# seven_segment_driver.net
KiCad netlist of a schematic drawn in Altium Designer
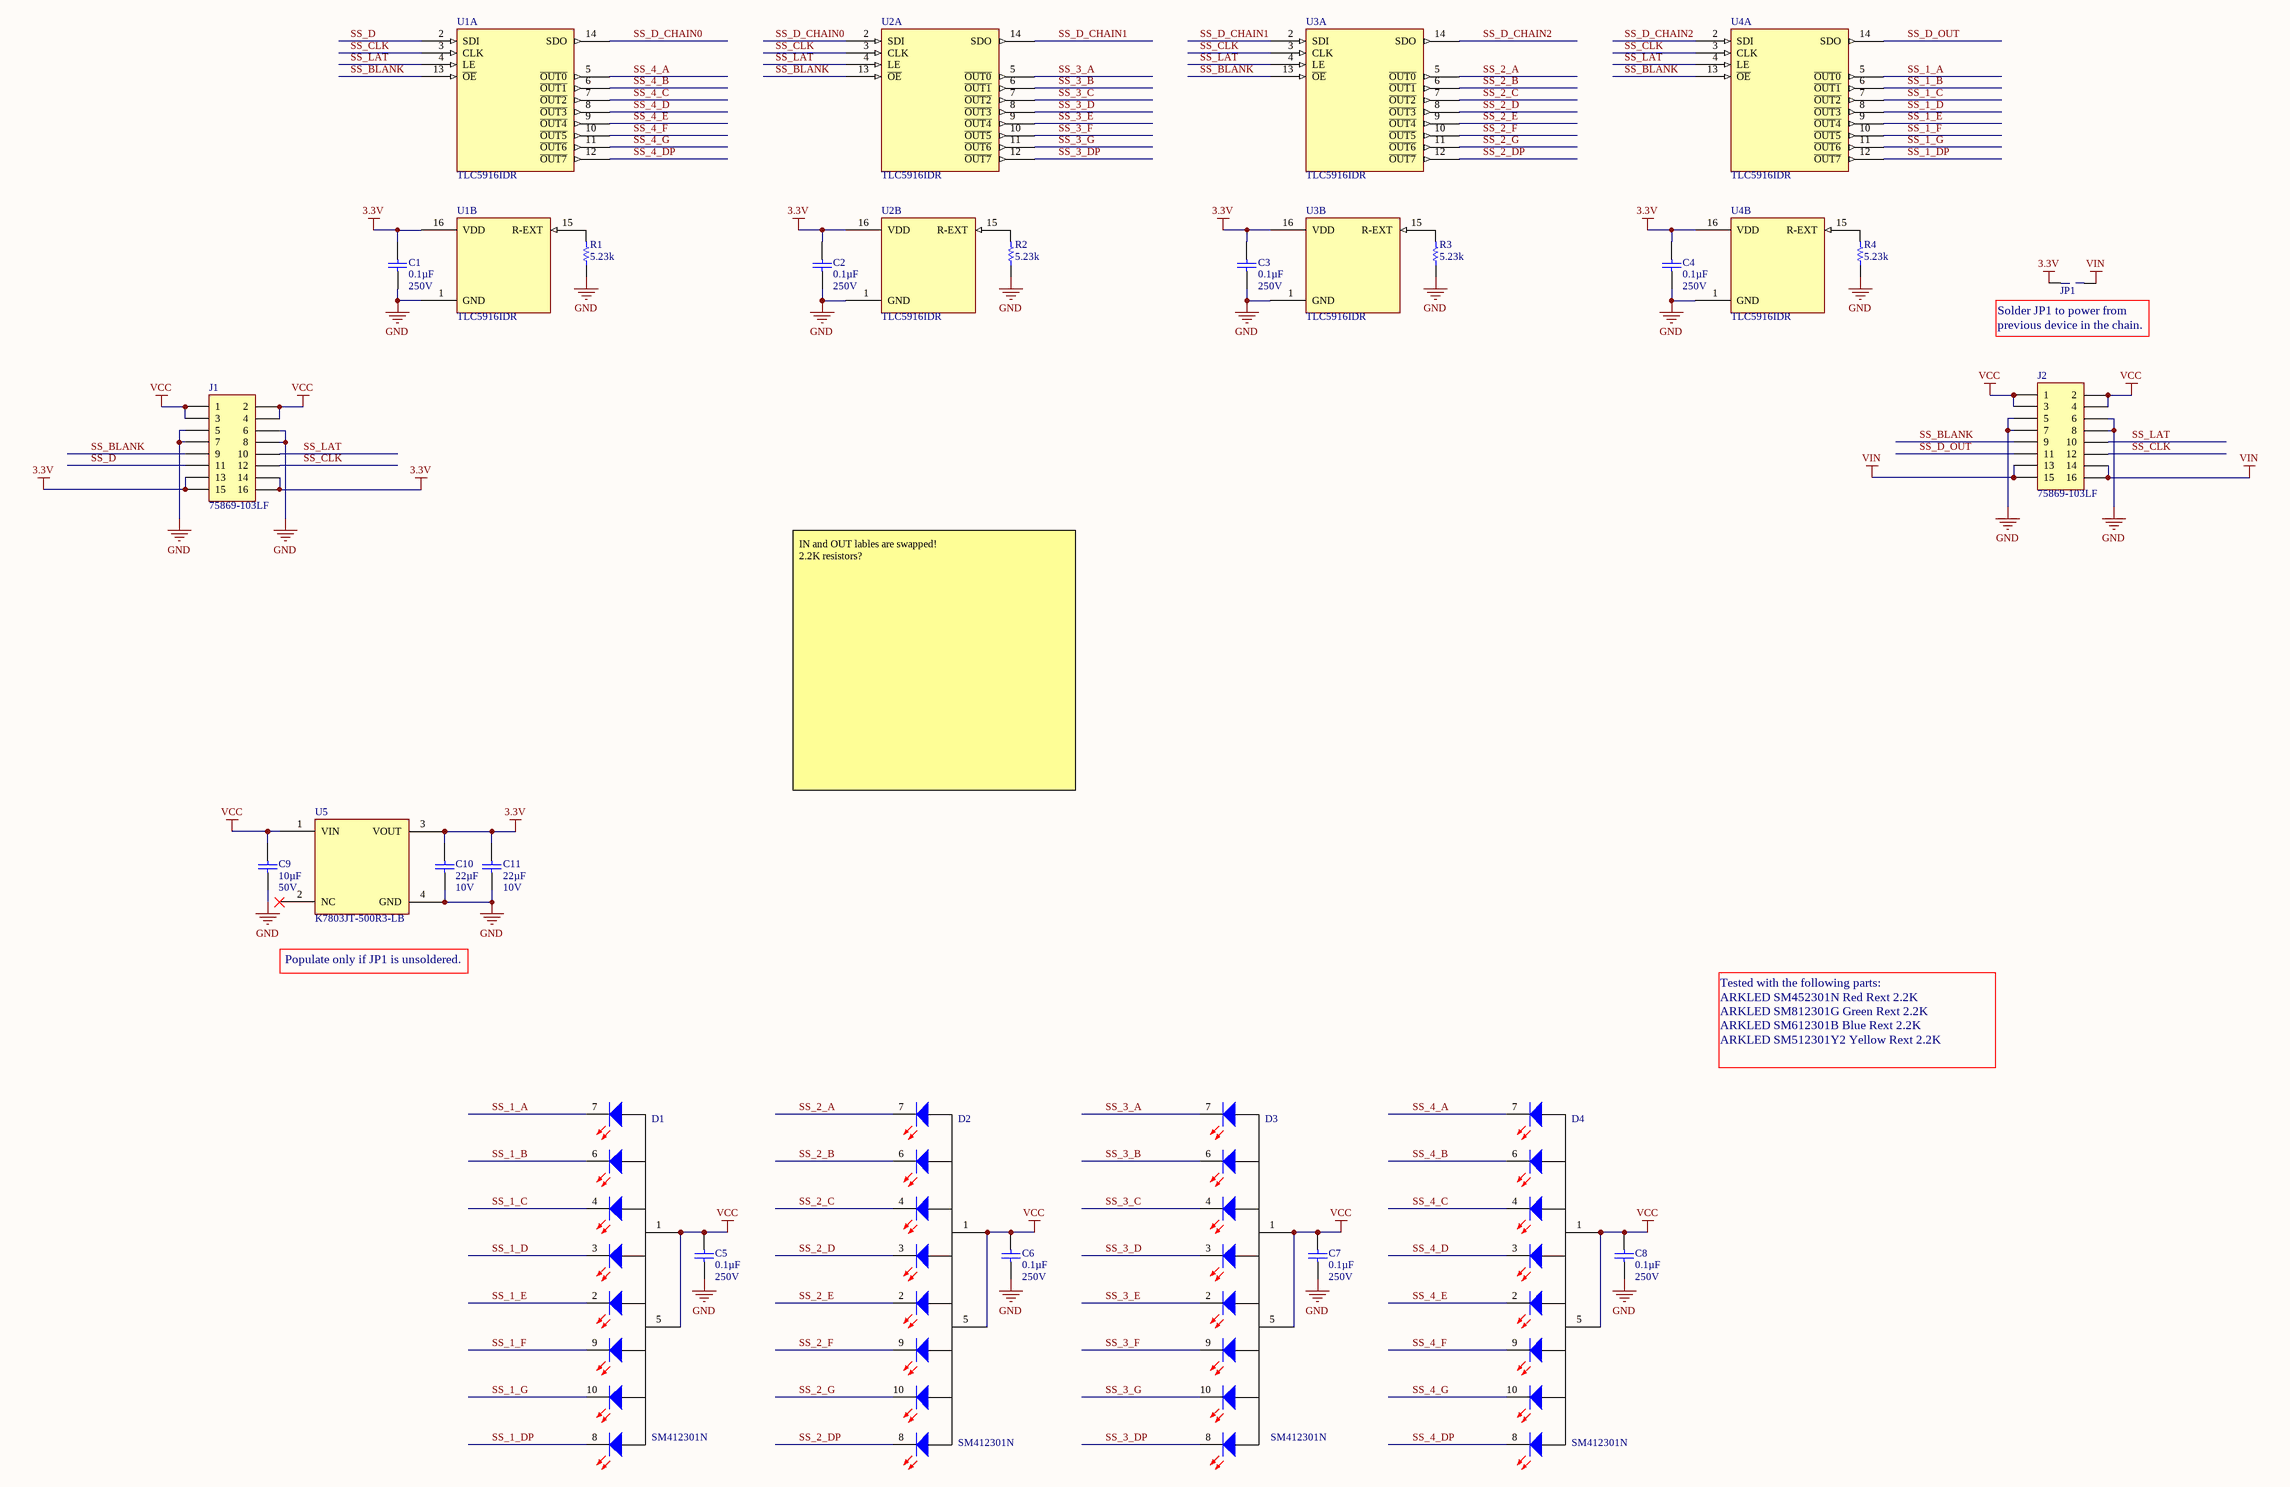
[diagram p0: seven_segment_driver.SchDoc]

(export (version "E")
  (design (tool "Eeschema 10.0.6"))
  (components
    (comp (ref "C1")
      (value "0.1µF")
      (footprint "Chip0805")
      (description "CAP CER 0.1UF 250V 10% X7T 0805")
      (fields
        (field (name "VOLTAGE") "250V")
        (field (name "PARTNUMBER") "C2012X7T2E104K125AA")
        (field (name "MANUFACTURER") "TDK Corporation")
      )
      (libsource (lib "Passives") (part "CAP"))
    )
    (comp (ref "C2")
      (value "0.1µF")
      (footprint "Chip0805")
      (description "CAP CER 0.1UF 250V 10% X7T 0805")
      (fields
        (field (name "VOLTAGE") "250V")
        (field (name "PARTNUMBER") "C2012X7T2E104K125AA")
        (field (name "MANUFACTURER") "TDK Corporation")
      )
      (libsource (lib "Passives") (part "CAP"))
    )
    (comp (ref "C3")
      (value "0.1µF")
      (footprint "Chip0805")
      (description "CAP CER 0.1UF 250V 10% X7T 0805")
      (fields
        (field (name "VOLTAGE") "250V")
        (field (name "PARTNUMBER") "C2012X7T2E104K125AA")
        (field (name "MANUFACTURER") "TDK Corporation")
      )
      (libsource (lib "Passives") (part "CAP"))
    )
    (comp (ref "C4")
      (value "0.1µF")
      (footprint "Chip0805")
      (description "CAP CER 0.1UF 250V 10% X7T 0805")
      (fields
        (field (name "VOLTAGE") "250V")
        (field (name "PARTNUMBER") "C2012X7T2E104K125AA")
        (field (name "MANUFACTURER") "TDK Corporation")
      )
      (libsource (lib "Passives") (part "CAP"))
    )
    (comp (ref "C5")
      (value "0.1µF")
      (footprint "Chip0805")
      (description "CAP CER 0.1UF 250V 10% X7T 0805")
      (fields
        (field (name "VOLTAGE") "250V")
        (field (name "PARTNUMBER") "C2012X7T2E104K125AA")
        (field (name "MANUFACTURER") "TDK Corporation")
      )
      (libsource (lib "Passives") (part "CAP"))
    )
    (comp (ref "C6")
      (value "0.1µF")
      (footprint "Chip0805")
      (description "CAP CER 0.1UF 250V 10% X7T 0805")
      (fields
        (field (name "VOLTAGE") "250V")
        (field (name "PARTNUMBER") "C2012X7T2E104K125AA")
        (field (name "MANUFACTURER") "TDK Corporation")
      )
      (libsource (lib "Passives") (part "CAP"))
    )
    (comp (ref "C7")
      (value "0.1µF")
      (footprint "Chip0805")
      (description "CAP CER 0.1UF 250V 10% X7T 0805")
      (fields
        (field (name "VOLTAGE") "250V")
        (field (name "PARTNUMBER") "C2012X7T2E104K125AA")
        (field (name "MANUFACTURER") "TDK Corporation")
      )
      (libsource (lib "Passives") (part "CAP"))
    )
    (comp (ref "C8")
      (value "0.1µF")
      (footprint "Chip0805")
      (description "CAP CER 0.1UF 250V 10% X7T 0805")
      (fields
        (field (name "VOLTAGE") "250V")
        (field (name "PARTNUMBER") "C2012X7T2E104K125AA")
        (field (name "MANUFACTURER") "TDK Corporation")
      )
      (libsource (lib "Passives") (part "CAP"))
    )
    (comp (ref "C9")
      (value "10µF")
      (footprint "Chip1206")
      (description "CAP CER 10UF 50V 10% X5R 1206")
      (fields
        (field (name "VOLTAGE") "50V")
        (field (name "PARTNUMBER") "C3216X5R1H106K160AB")
        (field (name "MANUFACTURER") "TDK Corporation")
      )
      (libsource (lib "Passives") (part "CAP"))
    )
    (comp (ref "C10")
      (value "22µF")
      (footprint "Chip0805")
      (description "CAP CER 22UF 10V 20% X5R 0805")
      (fields
        (field (name "VOLTAGE") "10V")
        (field (name "PARTNUMBER") "C2012X5R1A226M085AC")
        (field (name "MANUFACTURER") "TDK Corporation")
      )
      (libsource (lib "Passives") (part "CAP"))
    )
    (comp (ref "C11")
      (value "22µF")
      (footprint "Chip0805")
      (description "CAP CER 22UF 10V 20% X5R 0805")
      (fields
        (field (name "VOLTAGE") "10V")
        (field (name "PARTNUMBER") "C2012X5R1A226M085AC")
        (field (name "MANUFACTURER") "TDK Corporation")
      )
      (libsource (lib "Passives") (part "CAP"))
    )
    (comp (ref "D1")
      (value "SM412301N")
      (footprint "seven_segment_2p3")
      (description "SEGMENTS DISPLAY 2.3\" COMMON ANODE")
      (fields (field (name "MANUFACTURER") "ARKLED"))
      (libsource (lib "Optoelectronics") (part "SEVEN_SEGMENT_ANODE"))
    )
    (comp (ref "D2")
      (value "SM412301N")
      (footprint "seven_segment_2p3")
      (description "SEGMENTS DISPLAY 2.3\" COMMON ANODE")
      (fields (field (name "MANUFACTURER") "ARKLED"))
      (libsource (lib "Optoelectronics") (part "SEVEN_SEGMENT_ANODE"))
    )
    (comp (ref "D3")
      (value "SM412301N")
      (footprint "seven_segment_2p3")
      (description "SEGMENTS DISPLAY 2.3\" COMMON ANODE")
      (fields (field (name "MANUFACTURER") "ARKLED"))
      (libsource (lib "Optoelectronics") (part "SEVEN_SEGMENT_ANODE"))
    )
    (comp (ref "D4")
      (value "SM412301N")
      (footprint "seven_segment_2p3")
      (description "SEGMENTS DISPLAY 2.3\" COMMON ANODE")
      (fields (field (name "MANUFACTURER") "ARKLED"))
      (libsource (lib "Optoelectronics") (part "SEVEN_SEGMENT_ANODE"))
    )
    (comp (ref "J1")
      (value "75869-103LF")
      (footprint "IDC_100_2x8")
      (description "CONN HEADER 16POS DUAL VERT PCB")
      (fields (field (name "MANUFACTURER") "FCI"))
      (libsource (lib "Connectors") (part "HEADER_2x8_ALT"))
    )
    (comp (ref "J2")
      (value "75869-103LF")
      (footprint "IDC_100_2x8")
      (description "CONN HEADER 16POS DUAL VERT PCB")
      (fields (field (name "MANUFACTURER") "FCI"))
      (libsource (lib "Connectors") (part "HEADER_2x8_ALT"))
    )
    (comp (ref "JP1")
      (value "JUMMPER_NO_CIRCLE")
      (footprint "JUMMPER_NO_CIRCLE")
      (libsource (lib "Mechanical") (part "JUMPER_NO"))
    )
    (comp (ref "R1")
      (value "5.23k")
      (footprint "Chip0805")
      (description "RES 5.23K OHM 1/8W 1% 0805 SMD")
      (fields (field (name "PARTNUMBER") "CRCW08055K23FKEA") (field (name "MANUFACTURER") "Vishay Dale"))
      (libsource (lib "Passives") (part "RES"))
    )
    (comp (ref "R2")
      (value "5.23k")
      (footprint "Chip0805")
      (description "RES 5.23K OHM 1/8W 1% 0805 SMD")
      (fields (field (name "PARTNUMBER") "CRCW08055K23FKEA") (field (name "MANUFACTURER") "Vishay Dale"))
      (libsource (lib "Passives") (part "RES"))
    )
    (comp (ref "R3")
      (value "5.23k")
      (footprint "Chip0805")
      (description "RES 5.23K OHM 1/8W 1% 0805 SMD")
      (fields (field (name "PARTNUMBER") "CRCW08055K23FKEA") (field (name "MANUFACTURER") "Vishay Dale"))
      (libsource (lib "Passives") (part "RES"))
    )
    (comp (ref "R4")
      (value "5.23k")
      (footprint "Chip0805")
      (description "RES 5.23K OHM 1/8W 1% 0805 SMD")
      (fields (field (name "PARTNUMBER") "CRCW08055K23FKEA") (field (name "MANUFACTURER") "Vishay Dale"))
      (libsource (lib "Passives") (part "RES"))
    )
    (comp (ref "U1")
      (value "TLC5916IDR")
      (footprint "16-SOIC")
      (description "IC LED DRVR LINEAR 120MA 16SOIC")
      (fields (field (name "MANUFACTURER") "Texas Instruments"))
      (libsource (lib "ICs") (part "TI_TLC591x"))
    )
    (comp (ref "U2")
      (value "TLC5916IDR")
      (footprint "16-SOIC")
      (description "IC LED DRVR LINEAR 120MA 16SOIC")
      (fields (field (name "MANUFACTURER") "Texas Instruments"))
      (libsource (lib "ICs") (part "TI_TLC591x"))
    )
    (comp (ref "U3")
      (value "TLC5916IDR")
      (footprint "16-SOIC")
      (description "IC LED DRVR LINEAR 120MA 16SOIC")
      (fields (field (name "MANUFACTURER") "Texas Instruments"))
      (libsource (lib "ICs") (part "TI_TLC591x"))
    )
    (comp (ref "U4")
      (value "TLC5916IDR")
      (footprint "16-SOIC")
      (description "IC LED DRVR LINEAR 120MA 16SOIC")
      (fields (field (name "MANUFACTURER") "Texas Instruments"))
      (libsource (lib "ICs") (part "TI_TLC591x"))
    )
    (comp (ref "U5")
      (value "K7803JT-500R3-LB")
      (footprint "MORNSUN_K78XXJT-500R3-LB")
      (description "LINEAR REGULATOR REPLACEMENT DC")
      (fields (field (name "MANUFACTURER") "Mornsun America, LLC"))
      (libsource (lib "ICs") (part "MORNSUN_K78XXJT-500R3-LB"))
    )
  )
  (nets
    (net (code "1") (name "/SS_1_A") (class "Default")
      (node (ref "D1") (pin "7") (pinfunction "A_7") (pintype "passive"))
      (node (ref "U4") (pin "5") (pinfunction "~{OUT0}_5") (pintype "output"))
    )
    (net (code "2") (name "/SS_1_B") (class "Default")
      (node (ref "D1") (pin "6") (pinfunction "B_6") (pintype "passive"))
      (node (ref "U4") (pin "6") (pinfunction "~{OUT1}_6") (pintype "output"))
    )
    (net (code "3") (name "/SS_1_C") (class "Default")
      (node (ref "D1") (pin "4") (pinfunction "C_4") (pintype "passive"))
      (node (ref "U4") (pin "7") (pinfunction "~{OUT2}_7") (pintype "output"))
    )
    (net (code "4") (name "/SS_1_D") (class "Default")
      (node (ref "D1") (pin "3") (pinfunction "D_3") (pintype "passive"))
      (node (ref "U4") (pin "8") (pinfunction "~{OUT3}_8") (pintype "output"))
    )
    (net (code "5") (name "/SS_1_DP") (class "Default")
      (node (ref "D1") (pin "8") (pinfunction "DP_8") (pintype "passive"))
      (node (ref "U4") (pin "12") (pinfunction "~{OUT7}_12") (pintype "output"))
    )
    (net (code "6") (name "/SS_1_E") (class "Default")
      (node (ref "D1") (pin "2") (pinfunction "E_2") (pintype "passive"))
      (node (ref "U4") (pin "9") (pinfunction "~{OUT4}_9") (pintype "output"))
    )
    (net (code "7") (name "/SS_1_F") (class "Default")
      (node (ref "D1") (pin "9") (pinfunction "F_9") (pintype "passive"))
      (node (ref "U4") (pin "10") (pinfunction "~{OUT5}_10") (pintype "output"))
    )
    (net (code "8") (name "/SS_1_G") (class "Default")
      (node (ref "D1") (pin "10") (pinfunction "G_10") (pintype "passive"))
      (node (ref "U4") (pin "11") (pinfunction "~{OUT6}_11") (pintype "output"))
    )
    (net (code "9") (name "/SS_2_A") (class "Default")
      (node (ref "D2") (pin "7") (pinfunction "A_7") (pintype "passive"))
      (node (ref "U3") (pin "5") (pinfunction "~{OUT0}_5") (pintype "output"))
    )
    (net (code "10") (name "/SS_2_B") (class "Default")
      (node (ref "D2") (pin "6") (pinfunction "B_6") (pintype "passive"))
      (node (ref "U3") (pin "6") (pinfunction "~{OUT1}_6") (pintype "output"))
    )
    (net (code "11") (name "/SS_2_C") (class "Default")
      (node (ref "D2") (pin "4") (pinfunction "C_4") (pintype "passive"))
      (node (ref "U3") (pin "7") (pinfunction "~{OUT2}_7") (pintype "output"))
    )
    (net (code "12") (name "/SS_2_D") (class "Default")
      (node (ref "D2") (pin "3") (pinfunction "D_3") (pintype "passive"))
      (node (ref "U3") (pin "8") (pinfunction "~{OUT3}_8") (pintype "output"))
    )
    (net (code "13") (name "/SS_2_DP") (class "Default")
      (node (ref "D2") (pin "8") (pinfunction "DP_8") (pintype "passive"))
      (node (ref "U3") (pin "12") (pinfunction "~{OUT7}_12") (pintype "output"))
    )
    (net (code "14") (name "/SS_2_E") (class "Default")
      (node (ref "D2") (pin "2") (pinfunction "E_2") (pintype "passive"))
      (node (ref "U3") (pin "9") (pinfunction "~{OUT4}_9") (pintype "output"))
    )
    (net (code "15") (name "/SS_2_F") (class "Default")
      (node (ref "D2") (pin "9") (pinfunction "F_9") (pintype "passive"))
      (node (ref "U3") (pin "10") (pinfunction "~{OUT5}_10") (pintype "output"))
    )
    (net (code "16") (name "/SS_2_G") (class "Default")
      (node (ref "D2") (pin "10") (pinfunction "G_10") (pintype "passive"))
      (node (ref "U3") (pin "11") (pinfunction "~{OUT6}_11") (pintype "output"))
    )
    (net (code "17") (name "/SS_3_A") (class "Default")
      (node (ref "D3") (pin "7") (pinfunction "A_7") (pintype "passive"))
      (node (ref "U2") (pin "5") (pinfunction "~{OUT0}_5") (pintype "output"))
    )
    (net (code "18") (name "/SS_3_B") (class "Default")
      (node (ref "D3") (pin "6") (pinfunction "B_6") (pintype "passive"))
      (node (ref "U2") (pin "6") (pinfunction "~{OUT1}_6") (pintype "output"))
    )
    (net (code "19") (name "/SS_3_C") (class "Default")
      (node (ref "D3") (pin "4") (pinfunction "C_4") (pintype "passive"))
      (node (ref "U2") (pin "7") (pinfunction "~{OUT2}_7") (pintype "output"))
    )
    (net (code "20") (name "/SS_3_D") (class "Default")
      (node (ref "D3") (pin "3") (pinfunction "D_3") (pintype "passive"))
      (node (ref "U2") (pin "8") (pinfunction "~{OUT3}_8") (pintype "output"))
    )
    (net (code "21") (name "/SS_3_DP") (class "Default")
      (node (ref "D3") (pin "8") (pinfunction "DP_8") (pintype "passive"))
      (node (ref "U2") (pin "12") (pinfunction "~{OUT7}_12") (pintype "output"))
    )
    (net (code "22") (name "/SS_3_E") (class "Default")
      (node (ref "D3") (pin "2") (pinfunction "E_2") (pintype "passive"))
      (node (ref "U2") (pin "9") (pinfunction "~{OUT4}_9") (pintype "output"))
    )
    (net (code "23") (name "/SS_3_F") (class "Default")
      (node (ref "D3") (pin "9") (pinfunction "F_9") (pintype "passive"))
      (node (ref "U2") (pin "10") (pinfunction "~{OUT5}_10") (pintype "output"))
    )
    (net (code "24") (name "/SS_3_G") (class "Default")
      (node (ref "D3") (pin "10") (pinfunction "G_10") (pintype "passive"))
      (node (ref "U2") (pin "11") (pinfunction "~{OUT6}_11") (pintype "output"))
    )
    (net (code "25") (name "/SS_4_A") (class "Default")
      (node (ref "D4") (pin "7") (pinfunction "A_7") (pintype "passive"))
      (node (ref "U1") (pin "5") (pinfunction "~{OUT0}_5") (pintype "output"))
    )
    (net (code "26") (name "/SS_4_B") (class "Default")
      (node (ref "D4") (pin "6") (pinfunction "B_6") (pintype "passive"))
      (node (ref "U1") (pin "6") (pinfunction "~{OUT1}_6") (pintype "output"))
    )
    (net (code "27") (name "/SS_4_C") (class "Default")
      (node (ref "D4") (pin "4") (pinfunction "C_4") (pintype "passive"))
      (node (ref "U1") (pin "7") (pinfunction "~{OUT2}_7") (pintype "output"))
    )
    (net (code "28") (name "/SS_4_D") (class "Default")
      (node (ref "D4") (pin "3") (pinfunction "D_3") (pintype "passive"))
      (node (ref "U1") (pin "8") (pinfunction "~{OUT3}_8") (pintype "output"))
    )
    (net (code "29") (name "/SS_4_DP") (class "Default")
      (node (ref "D4") (pin "8") (pinfunction "DP_8") (pintype "passive"))
      (node (ref "U1") (pin "12") (pinfunction "~{OUT7}_12") (pintype "output"))
    )
    (net (code "30") (name "/SS_4_E") (class "Default")
      (node (ref "D4") (pin "2") (pinfunction "E_2") (pintype "passive"))
      (node (ref "U1") (pin "9") (pinfunction "~{OUT4}_9") (pintype "output"))
    )
    (net (code "31") (name "/SS_4_F") (class "Default")
      (node (ref "D4") (pin "9") (pinfunction "F_9") (pintype "passive"))
      (node (ref "U1") (pin "10") (pinfunction "~{OUT5}_10") (pintype "output"))
    )
    (net (code "32") (name "/SS_4_G") (class "Default")
      (node (ref "D4") (pin "10") (pinfunction "G_10") (pintype "passive"))
      (node (ref "U1") (pin "11") (pinfunction "~{OUT6}_11") (pintype "output"))
    )
    (net (code "33") (name "/SS_BLANK") (class "Default")
      (node (ref "J1") (pin "9") (pinfunction "9_9") (pintype "passive"))
      (node (ref "J2") (pin "9") (pinfunction "9_9") (pintype "passive"))
      (node (ref "U1") (pin "13") (pinfunction "~{OE}_13") (pintype "input"))
      (node (ref "U2") (pin "13") (pinfunction "~{OE}_13") (pintype "input"))
      (node (ref "U3") (pin "13") (pinfunction "~{OE}_13") (pintype "input"))
      (node (ref "U4") (pin "13") (pinfunction "~{OE}_13") (pintype "input"))
    )
    (net (code "34") (name "/SS_CLK") (class "Default")
      (node (ref "J1") (pin "12") (pinfunction "12_12") (pintype "passive"))
      (node (ref "J2") (pin "12") (pinfunction "12_12") (pintype "passive"))
      (node (ref "U1") (pin "3") (pinfunction "CLK_3") (pintype "input"))
      (node (ref "U2") (pin "3") (pinfunction "CLK_3") (pintype "input"))
      (node (ref "U3") (pin "3") (pinfunction "CLK_3") (pintype "input"))
      (node (ref "U4") (pin "3") (pinfunction "CLK_3") (pintype "input"))
    )
    (net (code "35") (name "/SS_D") (class "Default")
      (node (ref "J1") (pin "11") (pinfunction "11_11") (pintype "passive"))
      (node (ref "U1") (pin "2") (pinfunction "SDI_2") (pintype "input"))
    )
    (net (code "36") (name "/SS_D_CHAIN0") (class "Default")
      (node (ref "U1") (pin "14") (pinfunction "SDO_14") (pintype "output"))
      (node (ref "U2") (pin "2") (pinfunction "SDI_2") (pintype "input"))
    )
    (net (code "37") (name "/SS_D_CHAIN1") (class "Default")
      (node (ref "U2") (pin "14") (pinfunction "SDO_14") (pintype "output"))
      (node (ref "U3") (pin "2") (pinfunction "SDI_2") (pintype "input"))
    )
    (net (code "38") (name "/SS_D_CHAIN2") (class "Default")
      (node (ref "U3") (pin "14") (pinfunction "SDO_14") (pintype "output"))
      (node (ref "U4") (pin "2") (pinfunction "SDI_2") (pintype "input"))
    )
    (net (code "39") (name "/SS_D_OUT") (class "Default")
      (node (ref "J2") (pin "11") (pinfunction "11_11") (pintype "passive"))
      (node (ref "U4") (pin "14") (pinfunction "SDO_14") (pintype "output"))
    )
    (net (code "40") (name "/SS_LAT") (class "Default")
      (node (ref "J1") (pin "10") (pinfunction "10_10") (pintype "passive"))
      (node (ref "J2") (pin "10") (pinfunction "10_10") (pintype "passive"))
      (node (ref "U1") (pin "4") (pinfunction "LE_4") (pintype "input"))
      (node (ref "U2") (pin "4") (pinfunction "LE_4") (pintype "input"))
      (node (ref "U3") (pin "4") (pinfunction "LE_4") (pintype "input"))
      (node (ref "U4") (pin "4") (pinfunction "LE_4") (pintype "input"))
    )
    (net (code "41") (name "3.3V") (class "Default")
      (node (ref "C1") (pin "2") (pinfunction "2_2") (pintype "passive"))
      (node (ref "C10") (pin "2") (pinfunction "2_2") (pintype "passive"))
      (node (ref "C11") (pin "2") (pinfunction "2_2") (pintype "passive"))
      (node (ref "C2") (pin "2") (pinfunction "2_2") (pintype "passive"))
      (node (ref "C3") (pin "2") (pinfunction "2_2") (pintype "passive"))
      (node (ref "C4") (pin "2") (pinfunction "2_2") (pintype "passive"))
      (node (ref "J1") (pin "13") (pinfunction "13_13") (pintype "passive"))
      (node (ref "J1") (pin "14") (pinfunction "14_14") (pintype "passive"))
      (node (ref "J1") (pin "15") (pinfunction "15_15") (pintype "passive"))
      (node (ref "J1") (pin "16") (pinfunction "16_16") (pintype "passive"))
      (node (ref "JP1") (pin "2") (pinfunction "2_2") (pintype "passive"))
      (node (ref "U1") (pin "16") (pinfunction "VDD_16") (pintype "passive"))
      (node (ref "U2") (pin "16") (pinfunction "VDD_16") (pintype "passive"))
      (node (ref "U3") (pin "16") (pinfunction "VDD_16") (pintype "passive"))
      (node (ref "U4") (pin "16") (pinfunction "VDD_16") (pintype "passive"))
      (node (ref "U5") (pin "3") (pinfunction "VOUT_3") (pintype "passive"))
    )
    (net (code "42") (name "GND") (class "Default")
      (node (ref "C1") (pin "1") (pinfunction "1_1") (pintype "passive"))
      (node (ref "C10") (pin "1") (pinfunction "1_1") (pintype "passive"))
      (node (ref "C11") (pin "1") (pinfunction "1_1") (pintype "passive"))
      (node (ref "C2") (pin "1") (pinfunction "1_1") (pintype "passive"))
      (node (ref "C3") (pin "1") (pinfunction "1_1") (pintype "passive"))
      (node (ref "C4") (pin "1") (pinfunction "1_1") (pintype "passive"))
      (node (ref "C5") (pin "1") (pinfunction "1_1") (pintype "passive"))
      (node (ref "C6") (pin "1") (pinfunction "1_1") (pintype "passive"))
      (node (ref "C7") (pin "1") (pinfunction "1_1") (pintype "passive"))
      (node (ref "C8") (pin "1") (pinfunction "1_1") (pintype "passive"))
      (node (ref "C9") (pin "1") (pinfunction "1_1") (pintype "passive"))
      (node (ref "J1") (pin "5") (pinfunction "5_5") (pintype "passive"))
      (node (ref "J1") (pin "6") (pinfunction "6_6") (pintype "passive"))
      (node (ref "J1") (pin "7") (pinfunction "7_7") (pintype "passive"))
      (node (ref "J1") (pin "8") (pinfunction "8_8") (pintype "passive"))
      (node (ref "J2") (pin "5") (pinfunction "5_5") (pintype "passive"))
      (node (ref "J2") (pin "6") (pinfunction "6_6") (pintype "passive"))
      (node (ref "J2") (pin "7") (pinfunction "7_7") (pintype "passive"))
      (node (ref "J2") (pin "8") (pinfunction "8_8") (pintype "passive"))
      (node (ref "R1") (pin "1") (pinfunction "1_1") (pintype "passive"))
      (node (ref "R2") (pin "1") (pinfunction "1_1") (pintype "passive"))
      (node (ref "R3") (pin "1") (pinfunction "1_1") (pintype "passive"))
      (node (ref "R4") (pin "1") (pinfunction "1_1") (pintype "passive"))
      (node (ref "U1") (pin "1") (pinfunction "GND_1") (pintype "passive"))
      (node (ref "U2") (pin "1") (pinfunction "GND_1") (pintype "passive"))
      (node (ref "U3") (pin "1") (pinfunction "GND_1") (pintype "passive"))
      (node (ref "U4") (pin "1") (pinfunction "GND_1") (pintype "passive"))
      (node (ref "U5") (pin "4") (pinfunction "GND_4") (pintype "passive"))
    )
    (net (code "43") (name "Net-(U1B-R-EXT)") (class "Default")
      (node (ref "R1") (pin "2") (pinfunction "2_2") (pintype "passive"))
      (node (ref "U1") (pin "15") (pinfunction "R-EXT_15") (pintype "input"))
    )
    (net (code "44") (name "Net-(U2B-R-EXT)") (class "Default")
      (node (ref "R2") (pin "2") (pinfunction "2_2") (pintype "passive"))
      (node (ref "U2") (pin "15") (pinfunction "R-EXT_15") (pintype "input"))
    )
    (net (code "45") (name "Net-(U3B-R-EXT)") (class "Default")
      (node (ref "R3") (pin "2") (pinfunction "2_2") (pintype "passive"))
      (node (ref "U3") (pin "15") (pinfunction "R-EXT_15") (pintype "input"))
    )
    (net (code "46") (name "Net-(U4B-R-EXT)") (class "Default")
      (node (ref "R4") (pin "2") (pinfunction "2_2") (pintype "passive"))
      (node (ref "U4") (pin "15") (pinfunction "R-EXT_15") (pintype "input"))
    )
    (net (code "47") (name "VCC") (class "Default")
      (node (ref "C5") (pin "2") (pinfunction "2_2") (pintype "passive"))
      (node (ref "C6") (pin "2") (pinfunction "2_2") (pintype "passive"))
      (node (ref "C7") (pin "2") (pinfunction "2_2") (pintype "passive"))
      (node (ref "C8") (pin "2") (pinfunction "2_2") (pintype "passive"))
      (node (ref "C9") (pin "2") (pinfunction "2_2") (pintype "passive"))
      (node (ref "D1") (pin "1") (pinfunction "A_1") (pintype "passive"))
      (node (ref "D1") (pin "5") (pinfunction "A_5") (pintype "passive"))
      (node (ref "D2") (pin "1") (pinfunction "A_1") (pintype "passive"))
      (node (ref "D2") (pin "5") (pinfunction "A_5") (pintype "passive"))
      (node (ref "D3") (pin "1") (pinfunction "A_1") (pintype "passive"))
      (node (ref "D3") (pin "5") (pinfunction "A_5") (pintype "passive"))
      (node (ref "D4") (pin "1") (pinfunction "A_1") (pintype "passive"))
      (node (ref "D4") (pin "5") (pinfunction "A_5") (pintype "passive"))
      (node (ref "J1") (pin "1") (pinfunction "1_1") (pintype "passive"))
      (node (ref "J1") (pin "2") (pinfunction "2_2") (pintype "passive"))
      (node (ref "J1") (pin "3") (pinfunction "3_3") (pintype "passive"))
      (node (ref "J1") (pin "4") (pinfunction "4_4") (pintype "passive"))
      (node (ref "J2") (pin "1") (pinfunction "1_1") (pintype "passive"))
      (node (ref "J2") (pin "2") (pinfunction "2_2") (pintype "passive"))
      (node (ref "J2") (pin "3") (pinfunction "3_3") (pintype "passive"))
      (node (ref "J2") (pin "4") (pinfunction "4_4") (pintype "passive"))
      (node (ref "U5") (pin "1") (pinfunction "VIN_1") (pintype "passive"))
    )
    (net (code "48") (name "VIN") (class "Default")
      (node (ref "J2") (pin "13") (pinfunction "13_13") (pintype "passive"))
      (node (ref "J2") (pin "14") (pinfunction "14_14") (pintype "passive"))
      (node (ref "J2") (pin "15") (pinfunction "15_15") (pintype "passive"))
      (node (ref "J2") (pin "16") (pinfunction "16_16") (pintype "passive"))
      (node (ref "JP1") (pin "1") (pinfunction "1_1") (pintype "passive"))
    )
    (net (code "49") (name "unconnected-(U5-NC-Pad2)") (class "Default")
      (node (ref "U5") (pin "2") (pinfunction "NC_2") (pintype "passive+no_connect"))
    )
  )
)
